# board.net
KiCad netlist of a schematic drawn in EAGLE
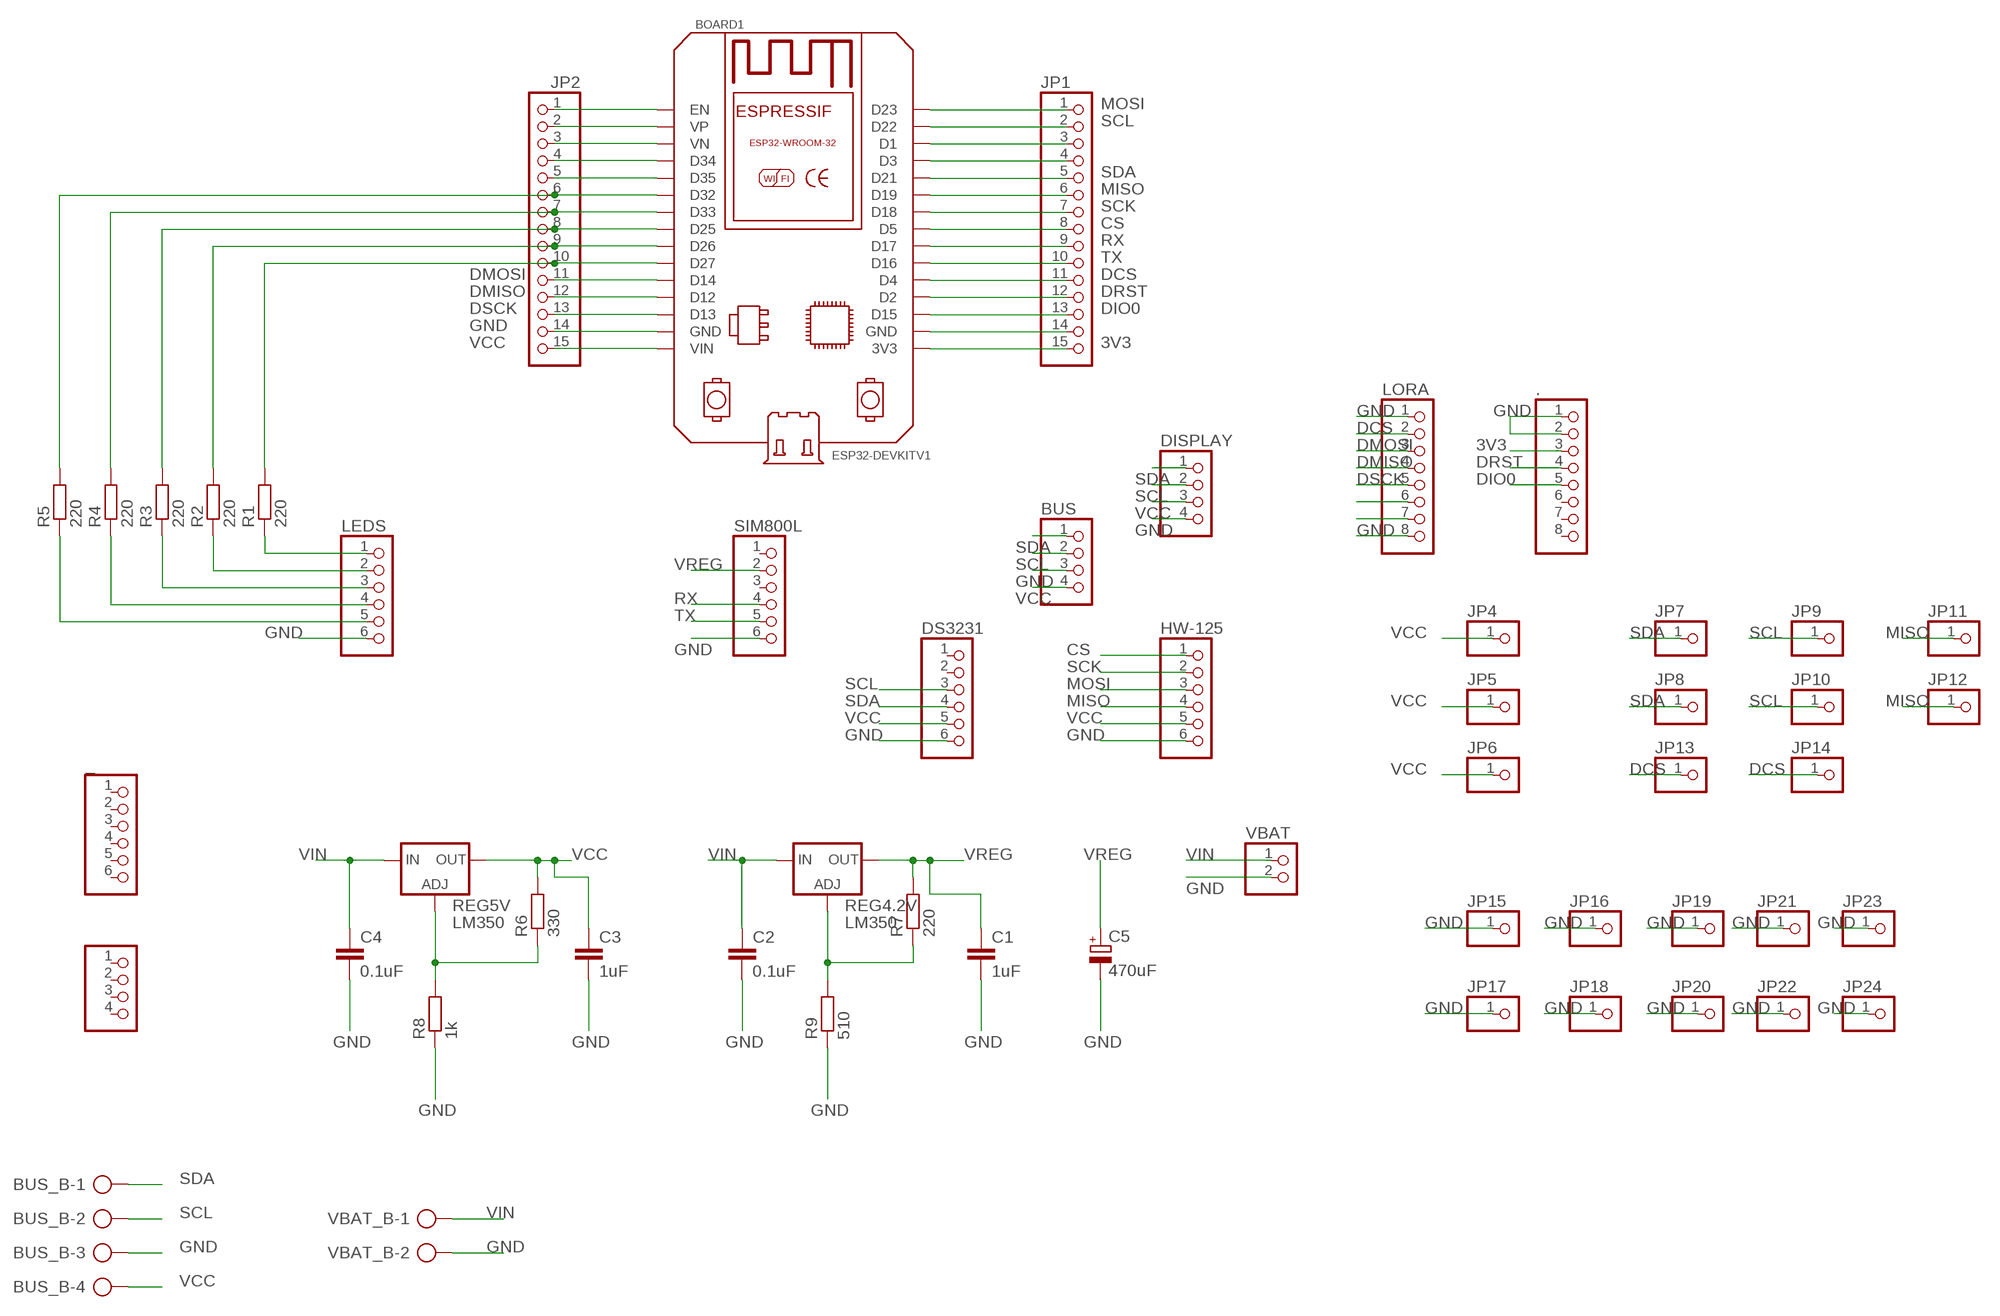
[diagram p0: schematic, sheet 1]

(export (version "E")
  (design (tool "Eeschema 10.0.6"))
  (components
    (comp (ref ".")
      (value "PINHD-1X8")
      (footprint "eagle-import:1X08")
      (libsource (lib "eagle-import") (part "PINHD-1X8"))
    )
    (comp (ref "BOARD1")
      (value "ESP32DEVKITV1")
      (footprint "eagle-import:ESP32-DEVKITV1")
      (libsource (lib "eagle-import") (part "ESP32DEVKITV1"))
    )
    (comp (ref "BUS")
      (value "PINHD-1X4")
      (footprint "eagle-import:1X04")
      (libsource (lib "eagle-import") (part "PINHD-1X4"))
    )
    (comp (ref "BUS_B")
      (value "AK500/4-H")
      (footprint "eagle-import:AK500_4-H")
      (libsource (lib "eagle-import") (part "AK500/4-H"))
    )
    (comp (ref "C1")
      (value "1uF")
      (footprint "eagle-import:C2.5-2")
      (libsource (lib "eagle-import") (part "C2.5/2"))
    )
    (comp (ref "C2")
      (value "0.1uF")
      (footprint "eagle-import:C2.5-2")
      (libsource (lib "eagle-import") (part "C2.5/2"))
    )
    (comp (ref "C3")
      (value "1uF")
      (footprint "eagle-import:C2.5-2")
      (libsource (lib "eagle-import") (part "C2.5/2"))
    )
    (comp (ref "C4")
      (value "0.1uF")
      (footprint "eagle-import:C2.5-2")
      (libsource (lib "eagle-import") (part "C2.5/2"))
    )
    (comp (ref "C5")
      (value "470uF")
      (footprint "eagle-import:E3,5-8")
      (libsource (lib "eagle-import") (part "CPOL-EUE3.5-8"))
    )
    (comp (ref "DISPLAY")
      (value "PINHD-1X4")
      (footprint "eagle-import:1X04")
      (libsource (lib "eagle-import") (part "PINHD-1X4"))
    )
    (comp (ref "DS3231")
      (value "PINHD-1X6")
      (footprint "eagle-import:1X06")
      (libsource (lib "eagle-import") (part "PINHD-1X6"))
    )
    (comp (ref "HW-125")
      (value "PINHD-1X6")
      (footprint "eagle-import:1X06")
      (libsource (lib "eagle-import") (part "PINHD-1X6"))
    )
    (comp (ref "JP1")
      (value "PINHD-1X15")
      (footprint "eagle-import:1X15")
      (libsource (lib "eagle-import") (part "PINHD-1X15"))
    )
    (comp (ref "JP2")
      (value "PINHD-1X15")
      (footprint "eagle-import:1X15")
      (libsource (lib "eagle-import") (part "PINHD-1X15"))
    )
    (comp (ref "JP3")
      (value "PINHD-1X4")
      (footprint "eagle-import:1X04")
      (libsource (lib "eagle-import") (part "PINHD-1X4"))
    )
    (comp (ref "JP4")
      (value "PINHD-1X1")
      (footprint "eagle-import:1X01")
      (libsource (lib "eagle-import") (part "PINHD-1X1"))
    )
    (comp (ref "JP5")
      (value "PINHD-1X1")
      (footprint "eagle-import:1X01")
      (libsource (lib "eagle-import") (part "PINHD-1X1"))
    )
    (comp (ref "JP6")
      (value "PINHD-1X1")
      (footprint "eagle-import:1X01")
      (libsource (lib "eagle-import") (part "PINHD-1X1"))
    )
    (comp (ref "JP7")
      (value "PINHD-1X1")
      (footprint "eagle-import:1X01")
      (libsource (lib "eagle-import") (part "PINHD-1X1"))
    )
    (comp (ref "JP8")
      (value "PINHD-1X1")
      (footprint "eagle-import:1X01")
      (libsource (lib "eagle-import") (part "PINHD-1X1"))
    )
    (comp (ref "JP9")
      (value "PINHD-1X1")
      (footprint "eagle-import:1X01")
      (libsource (lib "eagle-import") (part "PINHD-1X1"))
    )
    (comp (ref "JP10")
      (value "PINHD-1X1")
      (footprint "eagle-import:1X01")
      (libsource (lib "eagle-import") (part "PINHD-1X1"))
    )
    (comp (ref "JP11")
      (value "PINHD-1X1")
      (footprint "eagle-import:1X01")
      (libsource (lib "eagle-import") (part "PINHD-1X1"))
    )
    (comp (ref "JP12")
      (value "PINHD-1X1")
      (footprint "eagle-import:1X01")
      (libsource (lib "eagle-import") (part "PINHD-1X1"))
    )
    (comp (ref "JP13")
      (value "PINHD-1X1")
      (footprint "eagle-import:1X01")
      (libsource (lib "eagle-import") (part "PINHD-1X1"))
    )
    (comp (ref "JP14")
      (value "PINHD-1X1")
      (footprint "eagle-import:1X01")
      (libsource (lib "eagle-import") (part "PINHD-1X1"))
    )
    (comp (ref "JP15")
      (value "PINHD-1X1")
      (footprint "eagle-import:1X01")
      (libsource (lib "eagle-import") (part "PINHD-1X1"))
    )
    (comp (ref "JP16")
      (value "PINHD-1X1")
      (footprint "eagle-import:1X01")
      (libsource (lib "eagle-import") (part "PINHD-1X1"))
    )
    (comp (ref "JP17")
      (value "PINHD-1X1")
      (footprint "eagle-import:1X01")
      (libsource (lib "eagle-import") (part "PINHD-1X1"))
    )
    (comp (ref "JP18")
      (value "PINHD-1X1")
      (footprint "eagle-import:1X01")
      (libsource (lib "eagle-import") (part "PINHD-1X1"))
    )
    (comp (ref "JP19")
      (value "PINHD-1X1")
      (footprint "eagle-import:1X01")
      (libsource (lib "eagle-import") (part "PINHD-1X1"))
    )
    (comp (ref "JP20")
      (value "PINHD-1X1")
      (footprint "eagle-import:1X01")
      (libsource (lib "eagle-import") (part "PINHD-1X1"))
    )
    (comp (ref "JP21")
      (value "PINHD-1X1")
      (footprint "eagle-import:1X01")
      (libsource (lib "eagle-import") (part "PINHD-1X1"))
    )
    (comp (ref "JP22")
      (value "PINHD-1X1")
      (footprint "eagle-import:1X01")
      (libsource (lib "eagle-import") (part "PINHD-1X1"))
    )
    (comp (ref "JP23")
      (value "PINHD-1X1")
      (footprint "eagle-import:1X01")
      (libsource (lib "eagle-import") (part "PINHD-1X1"))
    )
    (comp (ref "JP24")
      (value "PINHD-1X1")
      (footprint "eagle-import:1X01")
      (libsource (lib "eagle-import") (part "PINHD-1X1"))
    )
    (comp (ref "LEDS")
      (value "PINHD-1X6")
      (footprint "eagle-import:1X06")
      (libsource (lib "eagle-import") (part "PINHD-1X6"))
    )
    (comp (ref "LORA")
      (value "PINHD-1X8")
      (footprint "eagle-import:1X08")
      (libsource (lib "eagle-import") (part "PINHD-1X8"))
    )
    (comp (ref "R1")
      (value "220")
      (footprint "eagle-import:R1206")
      (libsource (lib "eagle-import") (part "R-EU_R1206"))
    )
    (comp (ref "R2")
      (value "220")
      (footprint "eagle-import:R1206")
      (libsource (lib "eagle-import") (part "R-EU_R1206"))
    )
    (comp (ref "R3")
      (value "220")
      (footprint "eagle-import:R1206")
      (libsource (lib "eagle-import") (part "R-EU_R1206"))
    )
    (comp (ref "R4")
      (value "220")
      (footprint "eagle-import:R1206")
      (libsource (lib "eagle-import") (part "R-EU_R1206"))
    )
    (comp (ref "R5")
      (value "220")
      (footprint "eagle-import:R1206")
      (libsource (lib "eagle-import") (part "R-EU_R1206"))
    )
    (comp (ref "R6")
      (value "330")
      (footprint "eagle-import:0204_7")
      (libsource (lib "eagle-import") (part "R-EU_0204/7"))
    )
    (comp (ref "R7")
      (value "220")
      (footprint "eagle-import:0204_7")
      (libsource (lib "eagle-import") (part "R-EU_0204/7"))
    )
    (comp (ref "R8")
      (value "1k")
      (footprint "eagle-import:0204_7")
      (libsource (lib "eagle-import") (part "R-EU_0204/7"))
    )
    (comp (ref "R9")
      (value "510")
      (footprint "eagle-import:0204_7")
      (libsource (lib "eagle-import") (part "R-EU_0204/7"))
    )
    (comp (ref "REG4.2V")
      (value "LM350")
      (footprint "eagle-import:317TS")
      (libsource (lib "eagle-import") (part "LM317TS"))
    )
    (comp (ref "REG5V")
      (value "LM350")
      (footprint "eagle-import:317TS")
      (libsource (lib "eagle-import") (part "LM317TS"))
    )
    (comp (ref "SIM800L")
      (value "PINHD-1X6")
      (footprint "eagle-import:1X06")
      (libsource (lib "eagle-import") (part "PINHD-1X6"))
    )
    (comp (ref "VBAT")
      (value "PINHD-1X2")
      (footprint "eagle-import:1X02")
      (libsource (lib "eagle-import") (part "PINHD-1X2"))
    )
    (comp (ref "VBAT_B")
      (value "AK500/2-H")
      (footprint "eagle-import:AK500_2-H")
      (libsource (lib "eagle-import") (part "AK500/2-H"))
    )
    (comp (ref "_")
      (value "PINHD-1X6")
      (footprint "eagle-import:1X06")
      (libsource (lib "eagle-import") (part "PINHD-1X6"))
    )
  )
  (nets
    (net (code "1") (name "/3V3") (class "Default")
      (node (ref ".") (pin "3") (pinfunction "3_3") (pintype "passive"))
      (node (ref "BOARD1") (pin "3V3") (pinfunction "3V3_3V3") (pintype "bidirectional"))
      (node (ref "JP1") (pin "15") (pinfunction "15_15") (pintype "passive"))
    )
    (net (code "2") (name "/CS") (class "Default")
      (node (ref "BOARD1") (pin "D5") (pinfunction "D5_D5") (pintype "bidirectional"))
      (node (ref "HW-125") (pin "1") (pinfunction "1_1") (pintype "passive"))
      (node (ref "JP1") (pin "8") (pinfunction "8_8") (pintype "passive"))
    )
    (net (code "3") (name "/DCS") (class "Default")
      (node (ref "BOARD1") (pin "D4") (pinfunction "D4_D4") (pintype "bidirectional"))
      (node (ref "JP1") (pin "11") (pinfunction "11_11") (pintype "passive"))
      (node (ref "JP13") (pin "1") (pinfunction "1_1") (pintype "passive"))
      (node (ref "JP14") (pin "1") (pinfunction "1_1") (pintype "passive"))
      (node (ref "LORA") (pin "2") (pinfunction "2_2") (pintype "passive"))
    )
    (net (code "4") (name "/DIO0") (class "Default")
      (node (ref ".") (pin "5") (pinfunction "5_5") (pintype "passive"))
      (node (ref "BOARD1") (pin "D15") (pinfunction "D15_D15") (pintype "bidirectional"))
      (node (ref "JP1") (pin "13") (pinfunction "13_13") (pintype "passive"))
    )
    (net (code "5") (name "/DMISO") (class "Default")
      (node (ref "BOARD1") (pin "D12") (pinfunction "D12_D12") (pintype "bidirectional"))
      (node (ref "JP2") (pin "12") (pinfunction "12_12") (pintype "passive"))
      (node (ref "LORA") (pin "4") (pinfunction "4_4") (pintype "passive"))
    )
    (net (code "6") (name "/DMOSI") (class "Default")
      (node (ref "BOARD1") (pin "D14") (pinfunction "D14_D14") (pintype "bidirectional"))
      (node (ref "JP2") (pin "11") (pinfunction "11_11") (pintype "passive"))
      (node (ref "LORA") (pin "3") (pinfunction "3_3") (pintype "passive"))
    )
    (net (code "7") (name "/DRST") (class "Default")
      (node (ref ".") (pin "4") (pinfunction "4_4") (pintype "passive"))
      (node (ref "BOARD1") (pin "D2") (pinfunction "D2_D2") (pintype "bidirectional"))
      (node (ref "JP1") (pin "12") (pinfunction "12_12") (pintype "passive"))
    )
    (net (code "8") (name "/DSCK") (class "Default")
      (node (ref "BOARD1") (pin "D13") (pinfunction "D13_D13") (pintype "bidirectional"))
      (node (ref "JP2") (pin "13") (pinfunction "13_13") (pintype "passive"))
      (node (ref "LORA") (pin "5") (pinfunction "5_5") (pintype "passive"))
    )
    (net (code "9") (name "/GND") (class "Default")
      (node (ref ".") (pin "1") (pinfunction "1_1") (pintype "passive"))
      (node (ref ".") (pin "2") (pinfunction "2_2") (pintype "passive"))
      (node (ref "BOARD1") (pin "GND") (pinfunction "GND_GND") (pintype "bidirectional"))
      (node (ref "BUS") (pin "3") (pinfunction "3_3") (pintype "passive"))
      (node (ref "BUS_B") (pin "3") (pinfunction "KL_3") (pintype "passive"))
      (node (ref "C1") (pin "2") (pinfunction "2_2") (pintype "passive"))
      (node (ref "C2") (pin "2") (pinfunction "2_2") (pintype "passive"))
      (node (ref "C3") (pin "2") (pinfunction "2_2") (pintype "passive"))
      (node (ref "C4") (pin "2") (pinfunction "2_2") (pintype "passive"))
      (node (ref "C5") (pin "-") (pinfunction "-_-") (pintype "passive"))
      (node (ref "DISPLAY") (pin "4") (pinfunction "4_4") (pintype "passive"))
      (node (ref "DS3231") (pin "6") (pinfunction "6_6") (pintype "passive"))
      (node (ref "HW-125") (pin "6") (pinfunction "6_6") (pintype "passive"))
      (node (ref "JP15") (pin "1") (pinfunction "1_1") (pintype "passive"))
      (node (ref "JP16") (pin "1") (pinfunction "1_1") (pintype "passive"))
      (node (ref "JP17") (pin "1") (pinfunction "1_1") (pintype "passive"))
      (node (ref "JP18") (pin "1") (pinfunction "1_1") (pintype "passive"))
      (node (ref "JP19") (pin "1") (pinfunction "1_1") (pintype "passive"))
      (node (ref "JP2") (pin "14") (pinfunction "14_14") (pintype "passive"))
      (node (ref "JP20") (pin "1") (pinfunction "1_1") (pintype "passive"))
      (node (ref "JP21") (pin "1") (pinfunction "1_1") (pintype "passive"))
      (node (ref "JP22") (pin "1") (pinfunction "1_1") (pintype "passive"))
      (node (ref "JP23") (pin "1") (pinfunction "1_1") (pintype "passive"))
      (node (ref "JP24") (pin "1") (pinfunction "1_1") (pintype "passive"))
      (node (ref "LEDS") (pin "6") (pinfunction "6_6") (pintype "passive"))
      (node (ref "LORA") (pin "1") (pinfunction "1_1") (pintype "passive"))
      (node (ref "LORA") (pin "8") (pinfunction "8_8") (pintype "passive"))
      (node (ref "R8") (pin "1") (pinfunction "1_1") (pintype "passive"))
      (node (ref "R9") (pin "1") (pinfunction "1_1") (pintype "passive"))
      (node (ref "SIM800L") (pin "6") (pinfunction "6_6") (pintype "passive"))
      (node (ref "VBAT") (pin "2") (pinfunction "2_2") (pintype "passive"))
      (node (ref "VBAT_B") (pin "2") (pinfunction "KL_2") (pintype "passive"))
    )
    (net (code "10") (name "/MISO") (class "Default")
      (node (ref "BOARD1") (pin "D19") (pinfunction "D19_D19") (pintype "bidirectional"))
      (node (ref "HW-125") (pin "4") (pinfunction "4_4") (pintype "passive"))
      (node (ref "JP1") (pin "6") (pinfunction "6_6") (pintype "passive"))
      (node (ref "JP11") (pin "1") (pinfunction "1_1") (pintype "passive"))
      (node (ref "JP12") (pin "1") (pinfunction "1_1") (pintype "passive"))
    )
    (net (code "11") (name "/MOSI") (class "Default")
      (node (ref "BOARD1") (pin "D23") (pinfunction "D23_D23") (pintype "bidirectional"))
      (node (ref "HW-125") (pin "3") (pinfunction "3_3") (pintype "passive"))
      (node (ref "JP1") (pin "1") (pinfunction "1_1") (pintype "passive"))
    )
    (net (code "12") (name "/RX") (class "Default")
      (node (ref "BOARD1") (pin "D17") (pinfunction "D17_D17") (pintype "bidirectional"))
      (node (ref "JP1") (pin "9") (pinfunction "9_9") (pintype "passive"))
      (node (ref "SIM800L") (pin "4") (pinfunction "4_4") (pintype "passive"))
    )
    (net (code "13") (name "/SCK") (class "Default")
      (node (ref "BOARD1") (pin "D18") (pinfunction "D18_D18") (pintype "bidirectional"))
      (node (ref "HW-125") (pin "2") (pinfunction "2_2") (pintype "passive"))
      (node (ref "JP1") (pin "7") (pinfunction "7_7") (pintype "passive"))
    )
    (net (code "14") (name "/SCL") (class "Default")
      (node (ref "BOARD1") (pin "D22") (pinfunction "D22_D22") (pintype "bidirectional"))
      (node (ref "BUS") (pin "2") (pinfunction "2_2") (pintype "passive"))
      (node (ref "BUS_B") (pin "2") (pinfunction "KL_2") (pintype "passive"))
      (node (ref "DISPLAY") (pin "2") (pinfunction "2_2") (pintype "passive"))
      (node (ref "DS3231") (pin "3") (pinfunction "3_3") (pintype "passive"))
      (node (ref "JP1") (pin "2") (pinfunction "2_2") (pintype "passive"))
      (node (ref "JP10") (pin "1") (pinfunction "1_1") (pintype "passive"))
      (node (ref "JP9") (pin "1") (pinfunction "1_1") (pintype "passive"))
    )
    (net (code "15") (name "/SDA") (class "Default")
      (node (ref "BOARD1") (pin "D21") (pinfunction "D21_D21") (pintype "bidirectional"))
      (node (ref "BUS") (pin "1") (pinfunction "1_1") (pintype "passive"))
      (node (ref "BUS_B") (pin "1") (pinfunction "KL_1") (pintype "passive"))
      (node (ref "DISPLAY") (pin "1") (pinfunction "1_1") (pintype "passive"))
      (node (ref "DS3231") (pin "4") (pinfunction "4_4") (pintype "passive"))
      (node (ref "JP1") (pin "5") (pinfunction "5_5") (pintype "passive"))
      (node (ref "JP7") (pin "1") (pinfunction "1_1") (pintype "passive"))
      (node (ref "JP8") (pin "1") (pinfunction "1_1") (pintype "passive"))
    )
    (net (code "16") (name "/TX") (class "Default")
      (node (ref "BOARD1") (pin "D16") (pinfunction "D16_D16") (pintype "bidirectional"))
      (node (ref "JP1") (pin "10") (pinfunction "10_10") (pintype "passive"))
      (node (ref "SIM800L") (pin "5") (pinfunction "5_5") (pintype "passive"))
    )
    (net (code "17") (name "/VCC") (class "Default")
      (node (ref "BOARD1") (pin "VIN") (pinfunction "VIN_VIN") (pintype "bidirectional"))
      (node (ref "BUS") (pin "4") (pinfunction "4_4") (pintype "passive"))
      (node (ref "BUS_B") (pin "4") (pinfunction "KL_4") (pintype "passive"))
      (node (ref "C3") (pin "1") (pinfunction "1_1") (pintype "passive"))
      (node (ref "DISPLAY") (pin "3") (pinfunction "3_3") (pintype "passive"))
      (node (ref "DS3231") (pin "5") (pinfunction "5_5") (pintype "passive"))
      (node (ref "HW-125") (pin "5") (pinfunction "5_5") (pintype "passive"))
      (node (ref "JP2") (pin "15") (pinfunction "15_15") (pintype "passive"))
      (node (ref "JP4") (pin "1") (pinfunction "1_1") (pintype "passive"))
      (node (ref "JP5") (pin "1") (pinfunction "1_1") (pintype "passive"))
      (node (ref "JP6") (pin "1") (pinfunction "1_1") (pintype "passive"))
      (node (ref "R6") (pin "2") (pinfunction "2_2") (pintype "passive"))
      (node (ref "REG5V") (pin "2") (pinfunction "OUT_2") (pintype "passive"))
    )
    (net (code "18") (name "/VIN") (class "Default")
      (node (ref "C2") (pin "1") (pinfunction "1_1") (pintype "passive"))
      (node (ref "C4") (pin "1") (pinfunction "1_1") (pintype "passive"))
      (node (ref "REG4.2V") (pin "3") (pinfunction "IN_3") (pintype "input"))
      (node (ref "REG5V") (pin "3") (pinfunction "IN_3") (pintype "input"))
      (node (ref "VBAT") (pin "1") (pinfunction "1_1") (pintype "passive"))
      (node (ref "VBAT_B") (pin "1") (pinfunction "KL_1") (pintype "passive"))
    )
    (net (code "19") (name "/VREG") (class "Default")
      (node (ref "C1") (pin "1") (pinfunction "1_1") (pintype "passive"))
      (node (ref "C5") (pin "+") (pinfunction "+_+") (pintype "passive"))
      (node (ref "R7") (pin "2") (pinfunction "2_2") (pintype "passive"))
      (node (ref "REG4.2V") (pin "2") (pinfunction "OUT_2") (pintype "passive"))
      (node (ref "SIM800L") (pin "2") (pinfunction "2_2") (pintype "passive"))
    )
    (net (code "20") (name "Net-(BOARD1-GND-PadGND@1)") (class "Default")
      (node (ref "BOARD1") (pin "GND@1") (pinfunction "GND_GND@1") (pintype "bidirectional"))
      (node (ref "JP1") (pin "14") (pinfunction "14_14") (pintype "passive"))
    )
    (net (code "21") (name "Net-(BOARD1-PadD1)") (class "Default")
      (node (ref "BOARD1") (pin "D1") (pinfunction "D1_D1") (pintype "bidirectional"))
      (node (ref "JP1") (pin "3") (pinfunction "3_3") (pintype "passive"))
    )
    (net (code "22") (name "Net-(BOARD1-PadD3)") (class "Default")
      (node (ref "BOARD1") (pin "D3") (pinfunction "D3_D3") (pintype "bidirectional"))
      (node (ref "JP1") (pin "4") (pinfunction "4_4") (pintype "passive"))
    )
    (net (code "23") (name "Net-(BOARD1-PadD25)") (class "Default")
      (node (ref "BOARD1") (pin "D25") (pinfunction "D25_D25") (pintype "bidirectional"))
      (node (ref "JP2") (pin "8") (pinfunction "8_8") (pintype "passive"))
      (node (ref "R3") (pin "2") (pinfunction "2_2") (pintype "passive"))
    )
    (net (code "24") (name "Net-(BOARD1-PadD26)") (class "Default")
      (node (ref "BOARD1") (pin "D26") (pinfunction "D26_D26") (pintype "bidirectional"))
      (node (ref "JP2") (pin "9") (pinfunction "9_9") (pintype "passive"))
      (node (ref "R2") (pin "2") (pinfunction "2_2") (pintype "passive"))
    )
    (net (code "25") (name "Net-(BOARD1-PadD27)") (class "Default")
      (node (ref "BOARD1") (pin "D27") (pinfunction "D27_D27") (pintype "bidirectional"))
      (node (ref "JP2") (pin "10") (pinfunction "10_10") (pintype "passive"))
      (node (ref "R1") (pin "2") (pinfunction "2_2") (pintype "passive"))
    )
    (net (code "26") (name "Net-(BOARD1-PadD32)") (class "Default")
      (node (ref "BOARD1") (pin "D32") (pinfunction "D32_D32") (pintype "bidirectional"))
      (node (ref "JP2") (pin "6") (pinfunction "6_6") (pintype "passive"))
      (node (ref "R5") (pin "2") (pinfunction "2_2") (pintype "passive"))
    )
    (net (code "27") (name "Net-(BOARD1-PadD33)") (class "Default")
      (node (ref "BOARD1") (pin "D33") (pinfunction "D33_D33") (pintype "bidirectional"))
      (node (ref "JP2") (pin "7") (pinfunction "7_7") (pintype "passive"))
      (node (ref "R4") (pin "2") (pinfunction "2_2") (pintype "passive"))
    )
    (net (code "28") (name "Net-(BOARD1-PadD34)") (class "Default")
      (node (ref "BOARD1") (pin "D34") (pinfunction "D34_D34") (pintype "bidirectional"))
      (node (ref "JP2") (pin "4") (pinfunction "4_4") (pintype "passive"))
    )
    (net (code "29") (name "Net-(BOARD1-PadD35)") (class "Default")
      (node (ref "BOARD1") (pin "D35") (pinfunction "D35_D35") (pintype "bidirectional"))
      (node (ref "JP2") (pin "5") (pinfunction "5_5") (pintype "passive"))
    )
    (net (code "30") (name "Net-(BOARD1-PadEN)") (class "Default")
      (node (ref "BOARD1") (pin "EN") (pinfunction "EN_EN") (pintype "bidirectional"))
      (node (ref "JP2") (pin "1") (pinfunction "1_1") (pintype "passive"))
    )
    (net (code "31") (name "Net-(BOARD1-PadVN)") (class "Default")
      (node (ref "BOARD1") (pin "VN") (pinfunction "VN_VN") (pintype "bidirectional"))
      (node (ref "JP2") (pin "3") (pinfunction "3_3") (pintype "passive"))
    )
    (net (code "32") (name "Net-(BOARD1-PadVP)") (class "Default")
      (node (ref "BOARD1") (pin "VP") (pinfunction "VP_VP") (pintype "bidirectional"))
      (node (ref "JP2") (pin "2") (pinfunction "2_2") (pintype "passive"))
    )
    (net (code "33") (name "Net-(LEDS-Pad1)") (class "Default")
      (node (ref "LEDS") (pin "1") (pinfunction "1_1") (pintype "passive"))
      (node (ref "R1") (pin "1") (pinfunction "1_1") (pintype "passive"))
    )
    (net (code "34") (name "Net-(LEDS-Pad2)") (class "Default")
      (node (ref "LEDS") (pin "2") (pinfunction "2_2") (pintype "passive"))
      (node (ref "R2") (pin "1") (pinfunction "1_1") (pintype "passive"))
    )
    (net (code "35") (name "Net-(LEDS-Pad3)") (class "Default")
      (node (ref "LEDS") (pin "3") (pinfunction "3_3") (pintype "passive"))
      (node (ref "R3") (pin "1") (pinfunction "1_1") (pintype "passive"))
    )
    (net (code "36") (name "Net-(LEDS-Pad4)") (class "Default")
      (node (ref "LEDS") (pin "4") (pinfunction "4_4") (pintype "passive"))
      (node (ref "R4") (pin "1") (pinfunction "1_1") (pintype "passive"))
    )
    (net (code "37") (name "Net-(LEDS-Pad5)") (class "Default")
      (node (ref "LEDS") (pin "5") (pinfunction "5_5") (pintype "passive"))
      (node (ref "R5") (pin "1") (pinfunction "1_1") (pintype "passive"))
    )
    (net (code "38") (name "Net-(REG4.2V-ADJ)") (class "Default")
      (node (ref "R7") (pin "1") (pinfunction "1_1") (pintype "passive"))
      (node (ref "R9") (pin "2") (pinfunction "2_2") (pintype "passive"))
      (node (ref "REG4.2V") (pin "1") (pinfunction "ADJ_1") (pintype "input"))
    )
    (net (code "39") (name "Net-(REG5V-ADJ)") (class "Default")
      (node (ref "R6") (pin "1") (pinfunction "1_1") (pintype "passive"))
      (node (ref "R8") (pin "2") (pinfunction "2_2") (pintype "passive"))
      (node (ref "REG5V") (pin "1") (pinfunction "ADJ_1") (pintype "input"))
    )
    (net (code "40") (name "unconnected-(.-Pad6)") (class "Default")
      (node (ref ".") (pin "6") (pinfunction "6_6") (pintype "passive"))
    )
    (net (code "41") (name "unconnected-(.-Pad7)") (class "Default")
      (node (ref ".") (pin "7") (pinfunction "7_7") (pintype "passive"))
    )
    (net (code "42") (name "unconnected-(.-Pad8)") (class "Default")
      (node (ref ".") (pin "8") (pinfunction "8_8") (pintype "passive"))
    )
    (net (code "43") (name "unconnected-(DS3231-Pad1)") (class "Default")
      (node (ref "DS3231") (pin "1") (pinfunction "1_1") (pintype "passive"))
    )
    (net (code "44") (name "unconnected-(DS3231-Pad2)") (class "Default")
      (node (ref "DS3231") (pin "2") (pinfunction "2_2") (pintype "passive"))
    )
    (net (code "45") (name "unconnected-(JP3-Pad1)") (class "Default")
      (node (ref "JP3") (pin "1") (pinfunction "1_1") (pintype "passive"))
    )
    (net (code "46") (name "unconnected-(JP3-Pad2)") (class "Default")
      (node (ref "JP3") (pin "2") (pinfunction "2_2") (pintype "passive"))
    )
    (net (code "47") (name "unconnected-(JP3-Pad3)") (class "Default")
      (node (ref "JP3") (pin "3") (pinfunction "3_3") (pintype "passive"))
    )
    (net (code "48") (name "unconnected-(JP3-Pad4)") (class "Default")
      (node (ref "JP3") (pin "4") (pinfunction "4_4") (pintype "passive"))
    )
    (net (code "49") (name "unconnected-(LORA-Pad6)") (class "Default")
      (node (ref "LORA") (pin "6") (pinfunction "6_6") (pintype "passive"))
    )
    (net (code "50") (name "unconnected-(LORA-Pad7)") (class "Default")
      (node (ref "LORA") (pin "7") (pinfunction "7_7") (pintype "passive"))
    )
    (net (code "51") (name "unconnected-(SIM800L-Pad1)") (class "Default")
      (node (ref "SIM800L") (pin "1") (pinfunction "1_1") (pintype "passive"))
    )
    (net (code "52") (name "unconnected-(SIM800L-Pad3)") (class "Default")
      (node (ref "SIM800L") (pin "3") (pinfunction "3_3") (pintype "passive"))
    )
    (net (code "53") (name "unconnected-(_-Pad1)") (class "Default")
      (node (ref "_") (pin "1") (pinfunction "1_1") (pintype "passive"))
    )
    (net (code "54") (name "unconnected-(_-Pad2)") (class "Default")
      (node (ref "_") (pin "2") (pinfunction "2_2") (pintype "passive"))
    )
    (net (code "55") (name "unconnected-(_-Pad3)") (class "Default")
      (node (ref "_") (pin "3") (pinfunction "3_3") (pintype "passive"))
    )
    (net (code "56") (name "unconnected-(_-Pad4)") (class "Default")
      (node (ref "_") (pin "4") (pinfunction "4_4") (pintype "passive"))
    )
    (net (code "57") (name "unconnected-(_-Pad5)") (class "Default")
      (node (ref "_") (pin "5") (pinfunction "5_5") (pintype "passive"))
    )
    (net (code "58") (name "unconnected-(_-Pad6)") (class "Default")
      (node (ref "_") (pin "6") (pinfunction "6_6") (pintype "passive"))
    )
  )
)
